# Sheet1.net
KiCad netlist of a schematic drawn in Altium Designer
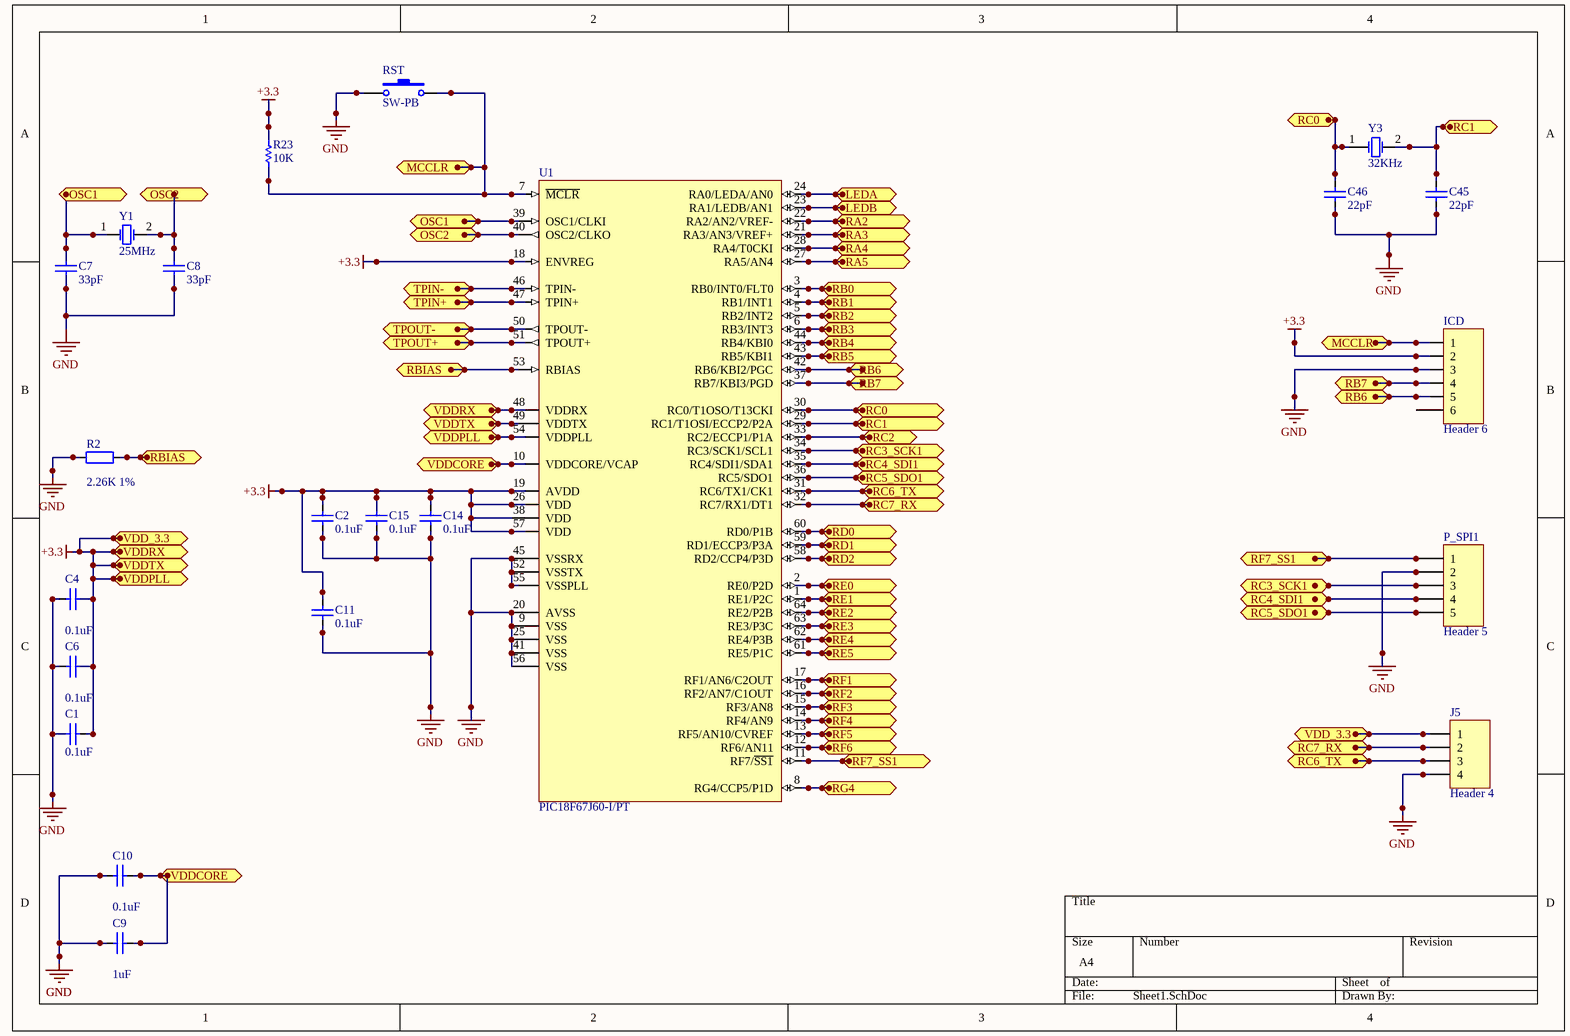
[diagram p0: Sheet1.SchDoc]

(export (version "E")
  (design (tool "Eeschema 10.0.6"))
  (components
    (comp (ref "C1")
      (value "0.1uF")
      (footprint "CAPC2012L")
      (description "Capacitor (Semiconductor SIM Model)")
      (fields (field (name "PUBLISHER") "Altium Limited"))
      (libsource (lib "Miscellaneous Devices") (part "Cap Semi"))
    )
    (comp (ref "C2")
      (value "0.1uF")
      (footprint "CAPC2012L")
      (description "Capacitor")
      (fields (field (name "PUBLISHER") "Altium Limited"))
      (libsource (lib "Miscellaneous Devices") (part "Cap"))
    )
    (comp (ref "C4")
      (value "0.1uF")
      (footprint "CAPC2012L")
      (description "Capacitor")
      (fields (field (name "PUBLISHER") "Altium Limited"))
      (libsource (lib "Miscellaneous Devices") (part "Cap"))
    )
    (comp (ref "C6")
      (value "0.1uF")
      (footprint "CAPC2012L")
      (description "Capacitor")
      (fields (field (name "PUBLISHER") "Altium Limited"))
      (libsource (lib "Miscellaneous Devices") (part "Cap"))
    )
    (comp (ref "C7")
      (value "33pF")
      (footprint "CAPC2012L")
      (description "Capacitor")
      (fields (field (name "PUBLISHER") "Altium Limited"))
      (libsource (lib "Miscellaneous Devices") (part "Cap"))
    )
    (comp (ref "C8")
      (value "33pF")
      (footprint "CAPC2012L")
      (description "Capacitor")
      (fields (field (name "PUBLISHER") "Altium Limited"))
      (libsource (lib "Miscellaneous Devices") (part "Cap"))
    )
    (comp (ref "C9")
      (value "1uF")
      (footprint "CAPC2012L")
      (description "Capacitor")
      (fields (field (name "PUBLISHER") "Altium Limited"))
      (libsource (lib "Miscellaneous Devices") (part "Cap"))
    )
    (comp (ref "C10")
      (value "0.1uF")
      (footprint "CAPC2012L")
      (description "Capacitor")
      (fields (field (name "PUBLISHER") "Altium Limited"))
      (libsource (lib "Miscellaneous Devices") (part "Cap"))
    )
    (comp (ref "C11")
      (value "0.1uF")
      (footprint "CAPC2012L")
      (description "Capacitor")
      (fields (field (name "PUBLISHER") "Altium Limited"))
      (libsource (lib "Miscellaneous Devices") (part "Cap"))
    )
    (comp (ref "C14")
      (value "0.1uF")
      (footprint "CAPC2012L")
      (description "Capacitor")
      (fields (field (name "PUBLISHER") "Altium Limited"))
      (libsource (lib "Miscellaneous Devices") (part "Cap"))
    )
    (comp (ref "C15")
      (value "0.1uF")
      (footprint "CAPC2012L")
      (description "Capacitor")
      (fields (field (name "PUBLISHER") "Altium Limited"))
      (libsource (lib "Miscellaneous Devices") (part "Cap"))
    )
    (comp (ref "C45")
      (value "22pF")
      (footprint "CAPC2012L")
      (description "Capacitor (Semiconductor SIM Model)")
      (fields (field (name "PUBLISHER") "Altium Limited"))
      (libsource (lib "Miscellaneous Devices") (part "Cap Semi"))
    )
    (comp (ref "C46")
      (value "22pF")
      (footprint "CAPC2012L")
      (description "Capacitor (Semiconductor SIM Model)")
      (fields (field (name "PUBLISHER") "Altium Limited"))
      (libsource (lib "Miscellaneous Devices") (part "Cap Semi"))
    )
    (comp (ref "ICD")
      (value "Header 6")
      (footprint "HDR1X6")
      (description "Header, 6-Pin")
      (fields (field (name "PUBLISHER") "Altium Limited"))
      (libsource (lib "Miscellaneous Connectors") (part "Header 6"))
    )
    (comp (ref "J5")
      (value "Header 4")
      (footprint "HDR1X4")
      (description "Header, 4-Pin")
      (fields (field (name "PUBLISHER") "Altium Limited"))
      (libsource (lib "Miscellaneous Connectors") (part "Header 4"))
    )
    (comp (ref "P_SPI1")
      (value "Header 5")
      (footprint "HDR1X5")
      (description "Header, 5-Pin")
      (fields (field (name "PUBLISHER") "Altium Limited"))
      (libsource (lib "Miscellaneous Connectors") (part "Header 5"))
    )
    (comp (ref "R2")
      (value "2.26K 1%")
      (footprint "RESC2012L")
      (description "Resistor")
      (fields (field (name "PUBLISHER") "Altium Limited"))
      (libsource (lib "Miscellaneous Devices") (part "Res2"))
    )
    (comp (ref "R23")
      (value "10K")
      (footprint "RESC3216L")
      (description "Semiconductor Resistor")
      (fields (field (name "PUBLISHER") "Altium Limited"))
      (libsource (lib "Miscellaneous Devices") (part "Res Semi"))
    )
    (comp (ref "RST")
      (value "SW-PB")
      (footprint "SPST-2")
      (description "Switch")
      (fields (field (name "PUBLISHER") "Altium Limited"))
      (libsource (lib "Miscellaneous Devices") (part "SW-PB"))
    )
    (comp (ref "U1")
      (value "PIC18F67J60-I/PT")
      (footprint "TQFP-PT64_L")
      (fields (field (name "PUBLISHER") "Altium Limited"))
      (libsource (lib "Microchip Microcontroller 8-Bit PIC18") (part "PIC18F67J60-I/PT"))
    )
    (comp (ref "Y1")
      (value "25MHz")
      (footprint "SPST-2")
      (description "Crystal Oscillator")
      (fields (field (name "PUBLISHER") "Altium Limited"))
      (libsource (lib "Miscellaneous Devices") (part "XTAL"))
    )
    (comp (ref "Y3")
      (value "32KHz")
      (footprint "BCY-W2/D3.1")
      (description "Crystal Oscillator")
      (fields (field (name "PUBLISHER") "Altium Limited"))
      (libsource (lib "Miscellaneous Devices") (part "XTAL"))
    )
  )
  (nets
    (net (code "1") (name "+3.3") (class "Default")
      (node (ref "C1") (pin "2") (pinfunction "2_2") (pintype "passive"))
      (node (ref "C11") (pin "2") (pinfunction "2_2") (pintype "passive"))
      (node (ref "C14") (pin "2") (pinfunction "2_2") (pintype "passive"))
      (node (ref "C15") (pin "2") (pinfunction "2_2") (pintype "passive"))
      (node (ref "C2") (pin "2") (pinfunction "2_2") (pintype "passive"))
      (node (ref "C4") (pin "2") (pinfunction "2_2") (pintype "passive"))
      (node (ref "C6") (pin "2") (pinfunction "2_2") (pintype "passive"))
      (node (ref "ICD") (pin "2") (pinfunction "2_2") (pintype "passive"))
      (node (ref "J5") (pin "1") (pinfunction "1_1") (pintype "passive"))
      (node (ref "R23") (pin "2") (pinfunction "2_2") (pintype "passive"))
      (node (ref "U1") (pin "18") (pinfunction "ENVREG_18") (pintype "input"))
      (node (ref "U1") (pin "19") (pinfunction "AVDD_19") (pintype "power_in"))
      (node (ref "U1") (pin "26") (pinfunction "VDD_26") (pintype "power_in"))
      (node (ref "U1") (pin "38") (pinfunction "VDD_38") (pintype "power_in"))
      (node (ref "U1") (pin "48") (pinfunction "VDDRX_48") (pintype "power_in"))
      (node (ref "U1") (pin "49") (pinfunction "VDDTX_49") (pintype "power_in"))
      (node (ref "U1") (pin "54") (pinfunction "VDDPLL_54") (pintype "power_in"))
      (node (ref "U1") (pin "57") (pinfunction "VDD_57") (pintype "power_in"))
    )
    (net (code "2") (name "/LEDA") (class "Default")
      (node (ref "U1") (pin "24") (pinfunction "RA0/LEDA/AN0_24") (pintype "bidirectional"))
    )
    (net (code "3") (name "/LEDB") (class "Default")
      (node (ref "U1") (pin "23") (pinfunction "RA1/LEDB/AN1_23") (pintype "bidirectional"))
    )
    (net (code "4") (name "/MCCLR") (class "Default")
      (node (ref "ICD") (pin "1") (pinfunction "1_1") (pintype "passive"))
      (node (ref "R23") (pin "1") (pinfunction "1_1") (pintype "passive"))
      (node (ref "RST") (pin "2") (pinfunction "2_2") (pintype "passive"))
      (node (ref "U1") (pin "7") (pinfunction "~{MCLR}_7") (pintype "input"))
    )
    (net (code "5") (name "/OSC1") (class "Default")
      (node (ref "U1") (pin "39") (pinfunction "OSC1/CLKI_39") (pintype "input"))
    )
    (net (code "6") (name "/OSC2") (class "Default")
      (node (ref "U1") (pin "40") (pinfunction "OSC2/CLKO_40") (pintype "output"))
    )
    (net (code "7") (name "/RA2") (class "Default")
      (node (ref "U1") (pin "22") (pinfunction "RA2/AN2/VREF-_22") (pintype "bidirectional"))
    )
    (net (code "8") (name "/RA3") (class "Default")
      (node (ref "U1") (pin "21") (pinfunction "RA3/AN3/VREF+_21") (pintype "bidirectional"))
    )
    (net (code "9") (name "/RA4") (class "Default")
      (node (ref "U1") (pin "28") (pinfunction "RA4/T0CKI_28") (pintype "bidirectional"))
    )
    (net (code "10") (name "/RA5") (class "Default")
      (node (ref "U1") (pin "27") (pinfunction "RA5/AN4_27") (pintype "bidirectional"))
    )
    (net (code "11") (name "/RB0") (class "Default")
      (node (ref "U1") (pin "3") (pinfunction "RB0/INT0/FLT0_3") (pintype "bidirectional"))
    )
    (net (code "12") (name "/RB1") (class "Default")
      (node (ref "U1") (pin "4") (pinfunction "RB1/INT1_4") (pintype "bidirectional"))
    )
    (net (code "13") (name "/RB2") (class "Default")
      (node (ref "U1") (pin "5") (pinfunction "RB2/INT2_5") (pintype "bidirectional"))
    )
    (net (code "14") (name "/RB3") (class "Default")
      (node (ref "U1") (pin "6") (pinfunction "RB3/INT3_6") (pintype "bidirectional"))
    )
    (net (code "15") (name "/RB4") (class "Default")
      (node (ref "U1") (pin "44") (pinfunction "RB4/KBI0_44") (pintype "bidirectional"))
    )
    (net (code "16") (name "/RB5") (class "Default")
      (node (ref "U1") (pin "43") (pinfunction "RB5/KBI1_43") (pintype "bidirectional"))
    )
    (net (code "17") (name "/RB6") (class "Default")
      (node (ref "ICD") (pin "5") (pinfunction "5_5") (pintype "passive"))
      (node (ref "U1") (pin "42") (pinfunction "RB6/KBI2/PGC_42") (pintype "bidirectional"))
    )
    (net (code "18") (name "/RB7") (class "Default")
      (node (ref "ICD") (pin "4") (pinfunction "4_4") (pintype "passive"))
      (node (ref "U1") (pin "37") (pinfunction "RB7/KBI3/PGD_37") (pintype "bidirectional"))
    )
    (net (code "19") (name "/RBIAS") (class "Default")
      (node (ref "R2") (pin "2") (pinfunction "2_2") (pintype "passive"))
      (node (ref "U1") (pin "53") (pinfunction "RBIAS_53") (pintype "input"))
    )
    (net (code "20") (name "/RC0") (class "Default")
      (node (ref "C46") (pin "2") (pinfunction "2_2") (pintype "passive"))
      (node (ref "U1") (pin "30") (pinfunction "RC0/T1OSO/T13CKI_30") (pintype "bidirectional"))
      (node (ref "Y3") (pin "1") (pinfunction "OSC1_1") (pintype "passive"))
    )
    (net (code "21") (name "/RC1") (class "Default")
      (node (ref "C45") (pin "2") (pinfunction "2_2") (pintype "passive"))
      (node (ref "U1") (pin "29") (pinfunction "RC1/T1OSI/ECCP2/P2A_29") (pintype "bidirectional"))
      (node (ref "Y3") (pin "2") (pinfunction "OSC2_2") (pintype "passive"))
    )
    (net (code "22") (name "/RC2") (class "Default")
      (node (ref "U1") (pin "33") (pinfunction "RC2/ECCP1/P1A_33") (pintype "bidirectional"))
    )
    (net (code "23") (name "/RC3_SCK1") (class "Default")
      (node (ref "P_SPI1") (pin "3") (pinfunction "3_3") (pintype "passive"))
      (node (ref "U1") (pin "34") (pinfunction "RC3/SCK1/SCL1_34") (pintype "bidirectional"))
    )
    (net (code "24") (name "/RC4_SDI1") (class "Default")
      (node (ref "P_SPI1") (pin "4") (pinfunction "4_4") (pintype "passive"))
      (node (ref "U1") (pin "35") (pinfunction "RC4/SDI1/SDA1_35") (pintype "bidirectional"))
    )
    (net (code "25") (name "/RC5_SDO1") (class "Default")
      (node (ref "P_SPI1") (pin "5") (pinfunction "5_5") (pintype "passive"))
      (node (ref "U1") (pin "36") (pinfunction "RC5/SDO1_36") (pintype "bidirectional"))
    )
    (net (code "26") (name "/RC6_TX") (class "Default")
      (node (ref "J5") (pin "3") (pinfunction "3_3") (pintype "passive"))
      (node (ref "U1") (pin "31") (pinfunction "RC6/TX1/CK1_31") (pintype "bidirectional"))
    )
    (net (code "27") (name "/RC7_RX") (class "Default")
      (node (ref "J5") (pin "2") (pinfunction "2_2") (pintype "passive"))
      (node (ref "U1") (pin "32") (pinfunction "RC7/RX1/DT1_32") (pintype "bidirectional"))
    )
    (net (code "28") (name "/RD0") (class "Default")
      (node (ref "U1") (pin "60") (pinfunction "RD0/P1B_60") (pintype "bidirectional"))
    )
    (net (code "29") (name "/RD1") (class "Default")
      (node (ref "U1") (pin "59") (pinfunction "RD1/ECCP3/P3A_59") (pintype "bidirectional"))
    )
    (net (code "30") (name "/RD2") (class "Default")
      (node (ref "U1") (pin "58") (pinfunction "RD2/CCP4/P3D_58") (pintype "bidirectional"))
    )
    (net (code "31") (name "/RE0") (class "Default")
      (node (ref "U1") (pin "2") (pinfunction "RE0/P2D_2") (pintype "bidirectional"))
    )
    (net (code "32") (name "/RE1") (class "Default")
      (node (ref "U1") (pin "1") (pinfunction "RE1/P2C_1") (pintype "bidirectional"))
    )
    (net (code "33") (name "/RE2") (class "Default")
      (node (ref "U1") (pin "64") (pinfunction "RE2/P2B_64") (pintype "bidirectional"))
    )
    (net (code "34") (name "/RE3") (class "Default")
      (node (ref "U1") (pin "63") (pinfunction "RE3/P3C_63") (pintype "bidirectional"))
    )
    (net (code "35") (name "/RE4") (class "Default")
      (node (ref "U1") (pin "62") (pinfunction "RE4/P3B_62") (pintype "bidirectional"))
    )
    (net (code "36") (name "/RE5") (class "Default")
      (node (ref "U1") (pin "61") (pinfunction "RE5/P1C_61") (pintype "bidirectional"))
    )
    (net (code "37") (name "/RF1") (class "Default")
      (node (ref "U1") (pin "17") (pinfunction "RF1/AN6/C2OUT_17") (pintype "bidirectional"))
    )
    (net (code "38") (name "/RF2") (class "Default")
      (node (ref "U1") (pin "16") (pinfunction "RF2/AN7/C1OUT_16") (pintype "bidirectional"))
    )
    (net (code "39") (name "/RF3") (class "Default")
      (node (ref "U1") (pin "15") (pinfunction "RF3/AN8_15") (pintype "bidirectional"))
    )
    (net (code "40") (name "/RF4") (class "Default")
      (node (ref "U1") (pin "14") (pinfunction "RF4/AN9_14") (pintype "bidirectional"))
    )
    (net (code "41") (name "/RF5") (class "Default")
      (node (ref "U1") (pin "13") (pinfunction "RF5/AN10/CVREF_13") (pintype "bidirectional"))
    )
    (net (code "42") (name "/RF6") (class "Default")
      (node (ref "U1") (pin "12") (pinfunction "RF6/AN11_12") (pintype "bidirectional"))
    )
    (net (code "43") (name "/RF7_SS1") (class "Default")
      (node (ref "P_SPI1") (pin "1") (pinfunction "1_1") (pintype "passive"))
      (node (ref "U1") (pin "11") (pinfunction "RF7/~{SS1}_11") (pintype "bidirectional"))
    )
    (net (code "44") (name "/RG4") (class "Default")
      (node (ref "U1") (pin "8") (pinfunction "RG4/CCP5/P1D_8") (pintype "bidirectional"))
    )
    (net (code "45") (name "/TPIN+") (class "Default")
      (node (ref "U1") (pin "47") (pinfunction "TPIN+_47") (pintype "input"))
    )
    (net (code "46") (name "/TPIN-") (class "Default")
      (node (ref "U1") (pin "46") (pinfunction "TPIN-_46") (pintype "input"))
    )
    (net (code "47") (name "/TPOUT+") (class "Default")
      (node (ref "U1") (pin "51") (pinfunction "TPOUT+_51") (pintype "output"))
    )
    (net (code "48") (name "/TPOUT-") (class "Default")
      (node (ref "U1") (pin "50") (pinfunction "TPOUT-_50") (pintype "output"))
    )
    (net (code "49") (name "/VDDCORE") (class "Default")
      (node (ref "C10") (pin "2") (pinfunction "2_2") (pintype "passive"))
      (node (ref "C9") (pin "2") (pinfunction "2_2") (pintype "passive"))
      (node (ref "U1") (pin "10") (pinfunction "VDDCORE/VCAP_10") (pintype "power_in"))
    )
    (net (code "50") (name "GND") (class "Default")
      (node (ref "C1") (pin "1") (pinfunction "1_1") (pintype "passive"))
      (node (ref "C10") (pin "1") (pinfunction "1_1") (pintype "passive"))
      (node (ref "C11") (pin "1") (pinfunction "1_1") (pintype "passive"))
      (node (ref "C14") (pin "1") (pinfunction "1_1") (pintype "passive"))
      (node (ref "C15") (pin "1") (pinfunction "1_1") (pintype "passive"))
      (node (ref "C2") (pin "1") (pinfunction "1_1") (pintype "passive"))
      (node (ref "C4") (pin "1") (pinfunction "1_1") (pintype "passive"))
      (node (ref "C45") (pin "1") (pinfunction "1_1") (pintype "passive"))
      (node (ref "C46") (pin "1") (pinfunction "1_1") (pintype "passive"))
      (node (ref "C6") (pin "1") (pinfunction "1_1") (pintype "passive"))
      (node (ref "C7") (pin "1") (pinfunction "1_1") (pintype "passive"))
      (node (ref "C8") (pin "1") (pinfunction "1_1") (pintype "passive"))
      (node (ref "C9") (pin "1") (pinfunction "1_1") (pintype "passive"))
      (node (ref "ICD") (pin "3") (pinfunction "3_3") (pintype "passive"))
      (node (ref "J5") (pin "4") (pinfunction "4_4") (pintype "passive"))
      (node (ref "P_SPI1") (pin "2") (pinfunction "2_2") (pintype "passive"))
      (node (ref "R2") (pin "1") (pinfunction "1_1") (pintype "passive"))
      (node (ref "RST") (pin "1") (pinfunction "1_1") (pintype "passive"))
      (node (ref "U1") (pin "20") (pinfunction "AVSS_20") (pintype "power_in"))
      (node (ref "U1") (pin "25") (pinfunction "VSS_25") (pintype "power_in"))
      (node (ref "U1") (pin "41") (pinfunction "VSS_41") (pintype "power_in"))
      (node (ref "U1") (pin "45") (pinfunction "VSSRX_45") (pintype "power_in"))
      (node (ref "U1") (pin "52") (pinfunction "VSSTX_52") (pintype "power_in"))
      (node (ref "U1") (pin "55") (pinfunction "VSSPLL_55") (pintype "power_in"))
      (node (ref "U1") (pin "56") (pinfunction "VSS_56") (pintype "power_in"))
      (node (ref "U1") (pin "9") (pinfunction "VSS_9") (pintype "power_in"))
    )
    (net (code "51") (name "Net-(Y1-OSC1)") (class "Default")
      (node (ref "C7") (pin "2") (pinfunction "2_2") (pintype "passive"))
      (node (ref "Y1") (pin "1") (pinfunction "OSC1_1") (pintype "passive"))
    )
    (net (code "52") (name "Net-(Y1-OSC2)") (class "Default")
      (node (ref "C8") (pin "2") (pinfunction "2_2") (pintype "passive"))
      (node (ref "Y1") (pin "2") (pinfunction "OSC2_2") (pintype "passive"))
    )
    (net (code "53") (name "unconnected-(ICD-Pad6)") (class "Default")
      (node (ref "ICD") (pin "6") (pinfunction "6_6") (pintype "passive"))
    )
  )
)
